# ToolheadPCBRemix.net
KiCad netlist of a schematic drawn in EAGLE
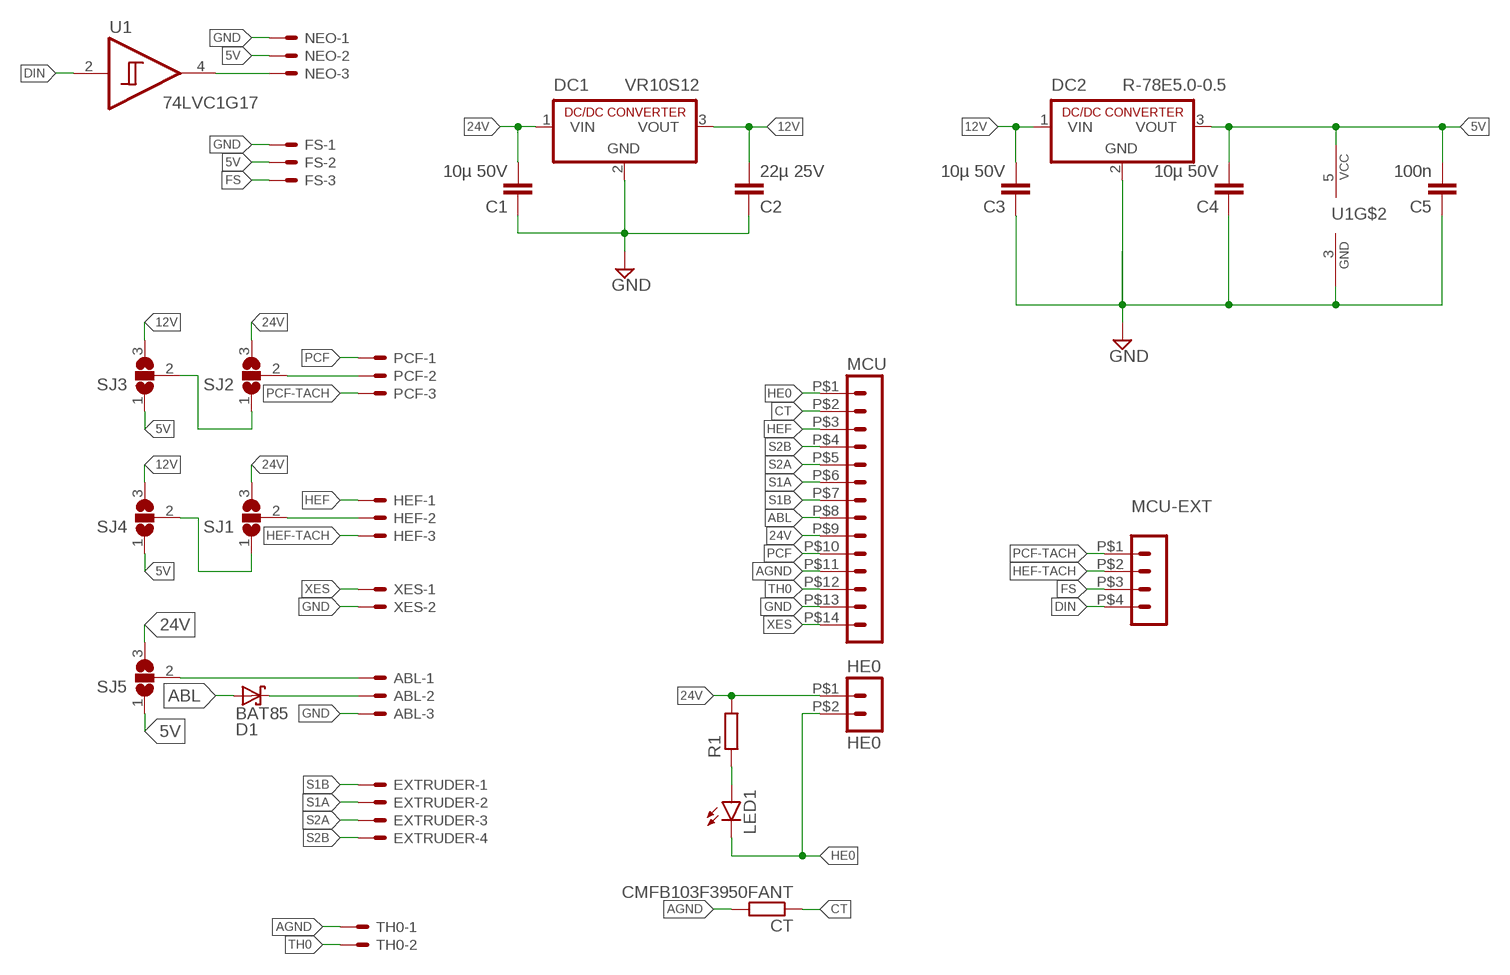
[diagram p0: schematic, sheet 1]

(export (version "E")
  (design (tool "Eeschema 10.0.6"))
  (components
    (comp (ref "ABL")
      (value "JST-XH-03-PIN-ROUND-PAD")
      (footprint "eagle-import:JST-XH-03-PACKAGE-ROUND-PAD")
      (libsource (lib "eagle-import") (part "JST-XH-03-PIN-ROUND-PAD"))
    )
    (comp (ref "C1")
      (value "10µ 50V")
      (footprint "eagle-import:C1206")
      (libsource (lib "eagle-import") (part "C-EUC1206"))
    )
    (comp (ref "C2")
      (value "22µ 25V")
      (footprint "eagle-import:C1206")
      (libsource (lib "eagle-import") (part "C-EUC1206"))
    )
    (comp (ref "C3")
      (value "10µ 50V")
      (footprint "eagle-import:C1206")
      (libsource (lib "eagle-import") (part "C-EUC1206"))
    )
    (comp (ref "C4")
      (value "10µ 50V")
      (footprint "eagle-import:C1206")
      (libsource (lib "eagle-import") (part "C-EUC1206"))
    )
    (comp (ref "C5")
      (value "100n")
      (footprint "eagle-import:C0805")
      (libsource (lib "eagle-import") (part "C-EUC0805"))
    )
    (comp (ref "CT")
      (value "CMFB103F3950FANT")
      (footprint "eagle-import:R0805")
      (libsource (lib "eagle-import") (part "R-EU_R0805"))
    )
    (comp (ref "D1")
      (value "BAT85")
      (footprint "eagle-import:SOD68")
      (libsource (lib "eagle-import") (part "BAT85"))
    )
    (comp (ref "DC1")
      (value "VR10S12")
      (footprint "eagle-import:SIP3")
      (libsource (lib "eagle-import") (part "R-78C-1.012"))
    )
    (comp (ref "DC2")
      (value "R-78E5.0-0.5")
      (footprint "eagle-import:SIP3")
      (libsource (lib "eagle-import") (part "R-78C-1.05.0"))
    )
    (comp (ref "EXTRUDER")
      (value "JST-XH-04-PIN-ROUND-PAD")
      (footprint "eagle-import:JST-XH-04-PACKAGE-ROUND-PAD")
      (libsource (lib "eagle-import") (part "JST-XH-04-PIN-ROUND-PAD"))
    )
    (comp (ref "FS")
      (value "JST-XH-03-PIN-ROUND-PAD")
      (footprint "eagle-import:JST-XH-03-PACKAGE-ROUND-PAD")
      (libsource (lib "eagle-import") (part "JST-XH-03-PIN-ROUND-PAD"))
    )
    (comp (ref "HE0")
      (value "HE0")
      (footprint "eagle-import:43650-0200")
      (libsource (lib "eagle-import") (part "HEADER_POS2_?43650-0200"))
    )
    (comp (ref "HEF")
      (value "JST-XH-03-PIN-ROUND-PAD")
      (footprint "eagle-import:JST-XH-03-PACKAGE-ROUND-PAD")
      (libsource (lib "eagle-import") (part "JST-XH-03-PIN-ROUND-PAD"))
    )
    (comp (ref "LED1")
      (value "LEDCHIPLED_0805")
      (footprint "eagle-import:CHIPLED_0805")
      (libsource (lib "eagle-import") (part "LEDCHIPLED_0805"))
    )
    (comp (ref "MCU")
      (value "HEADER_POS14_43045-1400")
      (footprint "eagle-import:43045-1400")
      (libsource (lib "eagle-import") (part "HEADER_POS14_?43045-1400"))
    )
    (comp (ref "MCU-EXT")
      (value "HEADER_POS4_43045-0401")
      (footprint "eagle-import:43045-0400")
      (libsource (lib "eagle-import") (part "HEADER_POS4_?43045-0401"))
    )
    (comp (ref "NEO")
      (value "JST-XH-03-PIN-ROUND-PAD")
      (footprint "eagle-import:JST-XH-03-PACKAGE-ROUND-PAD")
      (libsource (lib "eagle-import") (part "JST-XH-03-PIN-ROUND-PAD"))
    )
    (comp (ref "PCF")
      (value "JST-XH-03-PIN-ROUND-PAD")
      (footprint "eagle-import:JST-XH-03-PACKAGE-ROUND-PAD")
      (libsource (lib "eagle-import") (part "JST-XH-03-PIN-ROUND-PAD"))
    )
    (comp (ref "R1")
      (value "R-EU_R0805")
      (footprint "eagle-import:R0805")
      (libsource (lib "eagle-import") (part "R-EU_R0805"))
    )
    (comp (ref "SJ1")
      (value "SJ2W")
      (footprint "eagle-import:SJ_2")
      (libsource (lib "eagle-import") (part "SJ2W"))
    )
    (comp (ref "SJ2")
      (value "SJ2W")
      (footprint "eagle-import:SJ_2")
      (libsource (lib "eagle-import") (part "SJ2W"))
    )
    (comp (ref "SJ3")
      (value "SJ2W")
      (footprint "eagle-import:SJ_2")
      (libsource (lib "eagle-import") (part "SJ2W"))
    )
    (comp (ref "SJ4")
      (value "SJ2W")
      (footprint "eagle-import:SJ_2")
      (libsource (lib "eagle-import") (part "SJ2W"))
    )
    (comp (ref "SJ5")
      (value "SJ2W")
      (footprint "eagle-import:SJ_2")
      (libsource (lib "eagle-import") (part "SJ2W"))
    )
    (comp (ref "TH0")
      (value "JST-XH-02-PIN-ROUND-PAD")
      (footprint "eagle-import:JST-XH-02-PACKAGE-ROUND-PAD")
      (libsource (lib "eagle-import") (part "JST-XH-02-PIN-ROUND-PAD"))
    )
    (comp (ref "U1")
      (value "74LVC1G17")
      (footprint "eagle-import:SOT23-5")
      (libsource (lib "eagle-import") (part "74LVC1G17"))
    )
    (comp (ref "XES")
      (value "JST-XH-02-PIN-ROUND-PAD")
      (footprint "eagle-import:JST-XH-02-PACKAGE-ROUND-PAD")
      (libsource (lib "eagle-import") (part "JST-XH-02-PIN-ROUND-PAD"))
    )
  )
  (nets
    (net (code "1") (name "5V") (class "Default")
      (node (ref "C4") (pin "2") (pinfunction "2_2") (pintype "passive"))
      (node (ref "C5") (pin "2") (pinfunction "2_2") (pintype "passive"))
      (node (ref "DC2") (pin "3") (pinfunction "VOUT_3") (pintype "passive"))
      (node (ref "FS") (pin "2") (pinfunction "S_2") (pintype "passive"))
      (node (ref "NEO") (pin "2") (pinfunction "S_2") (pintype "passive"))
      (node (ref "SJ3") (pin "1") (pinfunction "1_1") (pintype "passive"))
      (node (ref "SJ4") (pin "1") (pinfunction "1_1") (pintype "passive"))
      (node (ref "SJ5") (pin "1") (pinfunction "1_1") (pintype "passive"))
      (node (ref "U1") (pin "5") (pinfunction "VCC_5") (pintype "power_in"))
    )
    (net (code "2") (name "12V") (class "Default")
      (node (ref "C2") (pin "2") (pinfunction "2_2") (pintype "passive"))
      (node (ref "C3") (pin "2") (pinfunction "2_2") (pintype "passive"))
      (node (ref "DC1") (pin "3") (pinfunction "VOUT_3") (pintype "passive"))
      (node (ref "DC2") (pin "1") (pinfunction "VIN_1") (pintype "passive"))
      (node (ref "SJ3") (pin "3") (pinfunction "3_3") (pintype "passive"))
      (node (ref "SJ4") (pin "3") (pinfunction "3_3") (pintype "passive"))
    )
    (net (code "3") (name "24V") (class "Default")
      (node (ref "C1") (pin "2") (pinfunction "2_2") (pintype "passive"))
      (node (ref "DC1") (pin "1") (pinfunction "VIN_1") (pintype "passive"))
      (node (ref "HE0") (pin "P$1") (pinfunction "1_P$1") (pintype "passive"))
      (node (ref "MCU") (pin "P$9") (pinfunction "9_P$9") (pintype "passive"))
      (node (ref "R1") (pin "2") (pinfunction "2_2") (pintype "passive"))
      (node (ref "SJ1") (pin "3") (pinfunction "3_3") (pintype "passive"))
      (node (ref "SJ2") (pin "3") (pinfunction "3_3") (pintype "passive"))
      (node (ref "SJ5") (pin "3") (pinfunction "3_3") (pintype "passive"))
    )
    (net (code "4") (name "ABL") (class "Default")
      (node (ref "D1") (pin "A") (pinfunction "A_A") (pintype "passive"))
      (node (ref "MCU") (pin "P$8") (pinfunction "8_P$8") (pintype "passive"))
    )
    (net (code "5") (name "AGND") (class "Default")
      (node (ref "CT") (pin "2") (pinfunction "2_2") (pintype "passive"))
      (node (ref "MCU") (pin "P$11") (pinfunction "11_P$11") (pintype "passive"))
      (node (ref "TH0") (pin "1") (pinfunction "S_1") (pintype "passive"))
    )
    (net (code "6") (name "CT") (class "Default")
      (node (ref "CT") (pin "1") (pinfunction "1_1") (pintype "passive"))
      (node (ref "MCU") (pin "P$2") (pinfunction "2_P$2") (pintype "passive"))
    )
    (net (code "7") (name "DIN") (class "Default")
      (node (ref "MCU-EXT") (pin "P$4") (pinfunction "4_P$4") (pintype "passive"))
      (node (ref "U1") (pin "2") (pinfunction "A_2") (pintype "input"))
    )
    (net (code "8") (name "FS") (class "Default")
      (node (ref "FS") (pin "3") (pinfunction "S_3") (pintype "passive"))
      (node (ref "MCU-EXT") (pin "P$3") (pinfunction "3_P$3") (pintype "passive"))
    )
    (net (code "9") (name "GND") (class "Default")
      (node (ref "ABL") (pin "3") (pinfunction "S_3") (pintype "passive"))
      (node (ref "C1") (pin "1") (pinfunction "1_1") (pintype "passive"))
      (node (ref "C2") (pin "1") (pinfunction "1_1") (pintype "passive"))
      (node (ref "C3") (pin "1") (pinfunction "1_1") (pintype "passive"))
      (node (ref "C4") (pin "1") (pinfunction "1_1") (pintype "passive"))
      (node (ref "C5") (pin "1") (pinfunction "1_1") (pintype "passive"))
      (node (ref "DC1") (pin "2") (pinfunction "GND_2") (pintype "passive"))
      (node (ref "DC2") (pin "2") (pinfunction "GND_2") (pintype "passive"))
      (node (ref "FS") (pin "1") (pinfunction "S_1") (pintype "passive"))
      (node (ref "MCU") (pin "P$13") (pinfunction "13_P$13") (pintype "passive"))
      (node (ref "NEO") (pin "1") (pinfunction "S_1") (pintype "passive"))
      (node (ref "U1") (pin "3") (pinfunction "GND_3") (pintype "power_in"))
      (node (ref "XES") (pin "2") (pinfunction "S_2") (pintype "passive"))
    )
    (net (code "10") (name "HE0") (class "Default")
      (node (ref "HE0") (pin "P$2") (pinfunction "2_P$2") (pintype "passive"))
      (node (ref "LED1") (pin "C") (pinfunction "C_C") (pintype "passive"))
      (node (ref "MCU") (pin "P$1") (pinfunction "1_P$1") (pintype "passive"))
    )
    (net (code "11") (name "HEF") (class "Default")
      (node (ref "HEF") (pin "1") (pinfunction "S_1") (pintype "passive"))
      (node (ref "MCU") (pin "P$3") (pinfunction "3_P$3") (pintype "passive"))
    )
    (net (code "12") (name "HEF-TACH") (class "Default")
      (node (ref "HEF") (pin "3") (pinfunction "S_3") (pintype "passive"))
      (node (ref "MCU-EXT") (pin "P$2") (pinfunction "2_P$2") (pintype "passive"))
    )
    (net (code "13") (name "Net-(ABLA-S)") (class "Default")
      (node (ref "ABL") (pin "1") (pinfunction "S_1") (pintype "passive"))
      (node (ref "SJ5") (pin "2") (pinfunction "2_2") (pintype "passive"))
    )
    (net (code "14") (name "Net-(ABLB-S)") (class "Default")
      (node (ref "ABL") (pin "2") (pinfunction "S_2") (pintype "passive"))
      (node (ref "D1") (pin "C") (pinfunction "K_C") (pintype "passive"))
    )
    (net (code "15") (name "Net-(HEFB-S)") (class "Default")
      (node (ref "HEF") (pin "2") (pinfunction "S_2") (pintype "passive"))
      (node (ref "SJ1") (pin "2") (pinfunction "2_2") (pintype "passive"))
    )
    (net (code "16") (name "Net-(LED1-PadA)") (class "Default")
      (node (ref "LED1") (pin "A") (pinfunction "A_A") (pintype "passive"))
      (node (ref "R1") (pin "1") (pinfunction "1_1") (pintype "passive"))
    )
    (net (code "17") (name "Net-(NEOC-S)") (class "Default")
      (node (ref "NEO") (pin "3") (pinfunction "S_3") (pintype "passive"))
      (node (ref "U1") (pin "4") (pinfunction "Y_4") (pintype "open_collector"))
    )
    (net (code "18") (name "Net-(PCFB-S)") (class "Default")
      (node (ref "PCF") (pin "2") (pinfunction "S_2") (pintype "passive"))
      (node (ref "SJ2") (pin "2") (pinfunction "2_2") (pintype "passive"))
    )
    (net (code "19") (name "Net-(SJ1-Pad1)") (class "Default")
      (node (ref "SJ1") (pin "1") (pinfunction "1_1") (pintype "passive"))
      (node (ref "SJ4") (pin "2") (pinfunction "2_2") (pintype "passive"))
    )
    (net (code "20") (name "Net-(SJ2-Pad1)") (class "Default")
      (node (ref "SJ2") (pin "1") (pinfunction "1_1") (pintype "passive"))
      (node (ref "SJ3") (pin "2") (pinfunction "2_2") (pintype "passive"))
    )
    (net (code "21") (name "PCF") (class "Default")
      (node (ref "MCU") (pin "P$10") (pinfunction "10_P$10") (pintype "passive"))
      (node (ref "PCF") (pin "1") (pinfunction "S_1") (pintype "passive"))
    )
    (net (code "22") (name "PCF-TACH") (class "Default")
      (node (ref "MCU-EXT") (pin "P$1") (pinfunction "1_P$1") (pintype "passive"))
      (node (ref "PCF") (pin "3") (pinfunction "S_3") (pintype "passive"))
    )
    (net (code "23") (name "S1A") (class "Default")
      (node (ref "EXTRUDER") (pin "2") (pinfunction "S_2") (pintype "passive"))
      (node (ref "MCU") (pin "P$6") (pinfunction "6_P$6") (pintype "passive"))
    )
    (net (code "24") (name "S1B") (class "Default")
      (node (ref "EXTRUDER") (pin "1") (pinfunction "S_1") (pintype "passive"))
      (node (ref "MCU") (pin "P$7") (pinfunction "7_P$7") (pintype "passive"))
    )
    (net (code "25") (name "S2A") (class "Default")
      (node (ref "EXTRUDER") (pin "3") (pinfunction "S_3") (pintype "passive"))
      (node (ref "MCU") (pin "P$5") (pinfunction "5_P$5") (pintype "passive"))
    )
    (net (code "26") (name "S2B") (class "Default")
      (node (ref "EXTRUDER") (pin "4") (pinfunction "S_4") (pintype "passive"))
      (node (ref "MCU") (pin "P$4") (pinfunction "4_P$4") (pintype "passive"))
    )
    (net (code "27") (name "TH0") (class "Default")
      (node (ref "MCU") (pin "P$12") (pinfunction "12_P$12") (pintype "passive"))
      (node (ref "TH0") (pin "2") (pinfunction "S_2") (pintype "passive"))
    )
    (net (code "28") (name "XES") (class "Default")
      (node (ref "MCU") (pin "P$14") (pinfunction "14_P$14") (pintype "passive"))
      (node (ref "XES") (pin "1") (pinfunction "S_1") (pintype "passive"))
    )
  )
)
